# ADS8688.net
KiCad netlist of a schematic drawn in Altium Designer
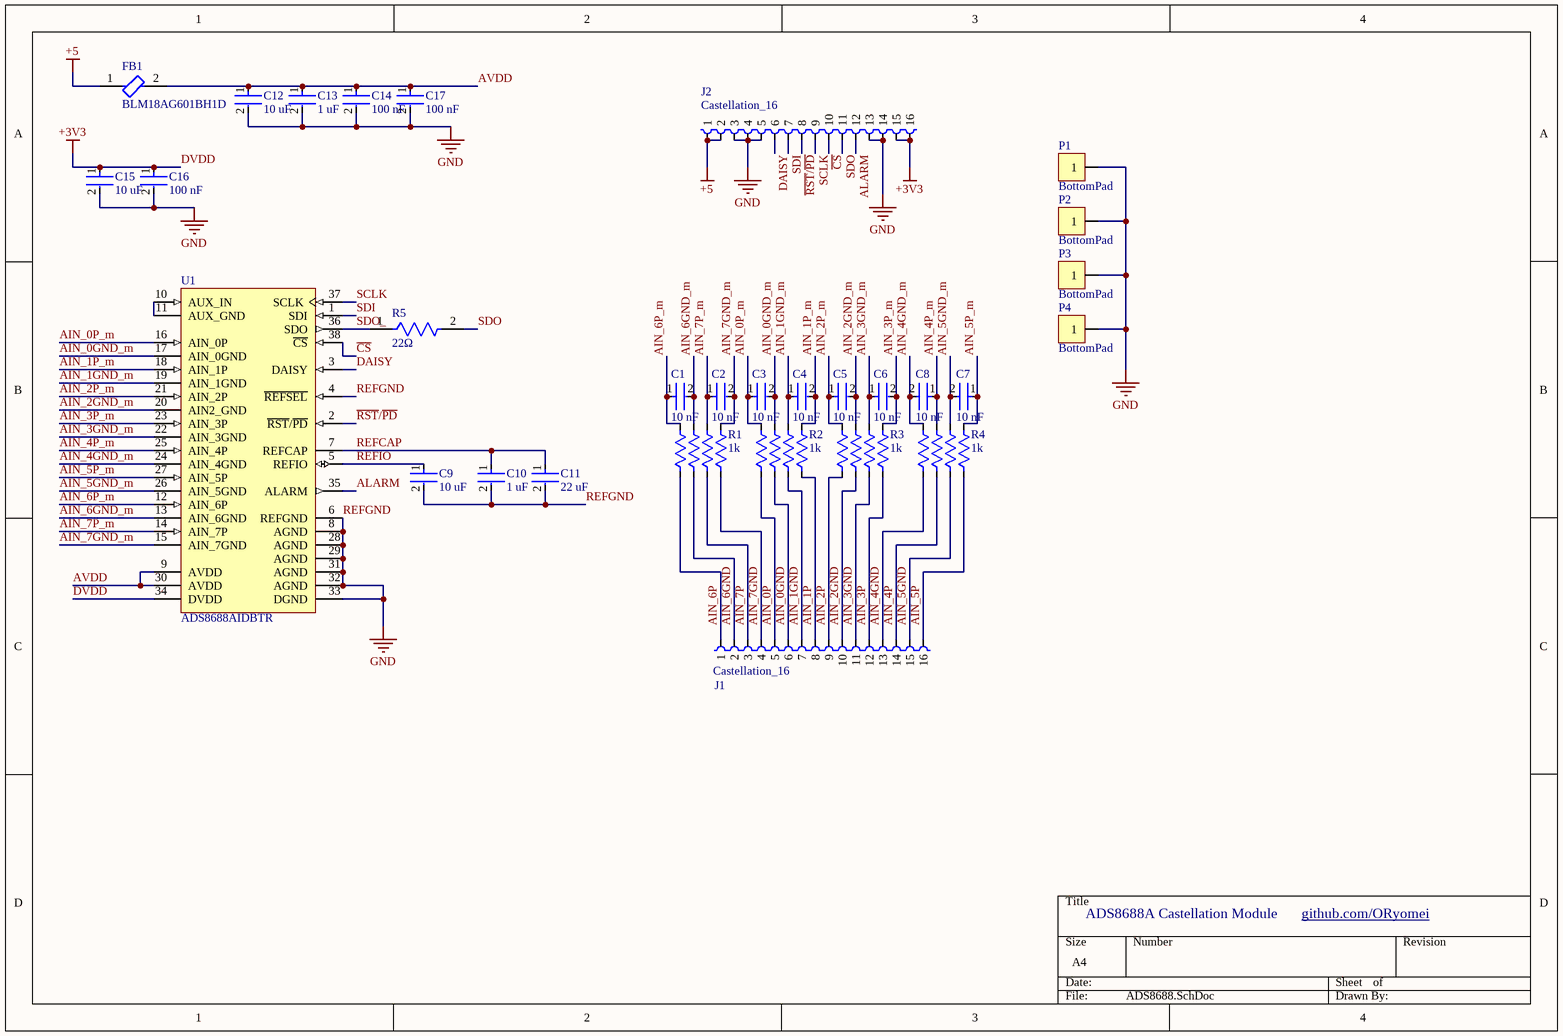
[diagram p0: ADS8688.SchDoc]

(export (version "E")
  (design (tool "Eeschema 10.0.6"))
  (components
    (comp (ref "C1")
      (value "10 nF")
      (footprint "FP-GRT188-0_1-e0_2_0_5-IPC_C")
      (description "Multi-Layer Ceramic Capacitor 10nF 25V C0G ±1% 0603 Paper T/R\r\nGRT1885C1E103FA02D\r\n0603")
      (libsource (lib "Altium Content Vault") (part "02cd4be3c70576c341d710602a673aa"))
    )
    (comp (ref "C2")
      (value "10 nF")
      (footprint "FP-GRT188-0_1-e0_2_0_5-IPC_C")
      (description "Multi-Layer Ceramic Capacitor 10nF 25V C0G ±1% 0603 Paper T/R\r\nGRT1885C1E103FA02D\r\n0603")
      (libsource (lib "Altium Content Vault") (part "02cd4be3c70576c341d710602a673aa"))
    )
    (comp (ref "C3")
      (value "10 nF")
      (footprint "FP-GRT188-0_1-e0_2_0_5-IPC_C")
      (description "Multi-Layer Ceramic Capacitor 10nF 25V C0G ±1% 0603 Paper T/R\r\nGRT1885C1E103FA02D\r\n0603")
      (libsource (lib "Altium Content Vault") (part "02cd4be3c70576c341d710602a673aa"))
    )
    (comp (ref "C4")
      (value "10 nF")
      (footprint "FP-GRT188-0_1-e0_2_0_5-IPC_C")
      (description "Multi-Layer Ceramic Capacitor 10nF 25V C0G ±1% 0603 Paper T/R\r\nGRT1885C1E103FA02D\r\n0603")
      (libsource (lib "Altium Content Vault") (part "02cd4be3c70576c341d710602a673aa"))
    )
    (comp (ref "C5")
      (value "10 nF")
      (footprint "FP-GRT188-0_1-e0_2_0_5-IPC_C")
      (description "Multi-Layer Ceramic Capacitor 10nF 25V C0G ±1% 0603 Paper T/R\r\nGRT1885C1E103FA02D\r\n0603")
      (libsource (lib "Altium Content Vault") (part "02cd4be3c70576c341d710602a673aa"))
    )
    (comp (ref "C6")
      (value "10 nF")
      (footprint "FP-GRT188-0_1-e0_2_0_5-IPC_C")
      (description "Multi-Layer Ceramic Capacitor 10nF 25V C0G ±1% 0603 Paper T/R\r\nGRT1885C1E103FA02D\r\n0603")
      (libsource (lib "Altium Content Vault") (part "02cd4be3c70576c341d710602a673aa"))
    )
    (comp (ref "C7")
      (value "10 nF")
      (footprint "FP-GRT188-0_1-e0_2_0_5-IPC_C")
      (description "Multi-Layer Ceramic Capacitor 10nF 25V C0G ±1% 0603 Paper T/R\r\nGRT1885C1E103FA02D\r\n0603")
      (libsource (lib "Altium Content Vault") (part "02cd4be3c70576c341d710602a673aa"))
    )
    (comp (ref "C8")
      (value "10 nF")
      (footprint "FP-GRT188-0_1-e0_2_0_5-IPC_C")
      (description "Multi-Layer Ceramic Capacitor 10nF 25V C0G ±1% 0603 Paper T/R\r\nGRT1885C1E103FA02D\r\n0603")
      (libsource (lib "Altium Content Vault") (part "02cd4be3c70576c341d710602a673aa"))
    )
    (comp (ref "C9")
      (value "10 uF")
      (footprint "FP-GRT188-0_2-MFG")
      (description "Multi-Layer Ceramic Capacitor 10uF 25V X5R ±20% 0603 Paper T/R\r\nGRT188R61E106ME13D\r\n10 uF")
      (fields (field (name "TOLERANCE") "20%"))
      (libsource (lib "Altium Content Vault") (part "02cd4be3c70576c341d710602a673aa"))
    )
    (comp (ref "C10")
      (value "1 uF")
      (footprint "FP-GRT188-0_1-e0_2_0_5-IPC_C")
      (description "Multi-Layer Ceramic Capacitor 1uF 25V X7R ±10% 0603 Paper T/R\r\nGRT188R71E105KE13D\r\n1 uF")
      (libsource (lib "Altium Content Vault") (part "02cd4be3c70576c341d710602a673aa"))
    )
    (comp (ref "C11")
      (value "22 uF")
      (footprint "FP-GRT21B-0_2-IPC_C")
      (description "Multi-Layer Ceramic Capacitor 22uF 25V X5R ±20% 0805 Emboss T/R\r\nGRT21BR61E226ME13L\r\n22 uF")
      (fields (field (name "TOLERANCE") "20%"))
      (libsource (lib "Altium Content Vault") (part "02cd4be3c70576c341d710602a673aa"))
    )
    (comp (ref "C12")
      (value "10 uF")
      (footprint "FP-GRT188-0_2-MFG")
      (description "Multi-Layer Ceramic Capacitor 10uF 25V X5R ±20% 0603 Paper T/R\r\nGRT188R61E106ME13D\r\n10 uF")
      (fields (field (name "TOLERANCE") "20%"))
      (libsource (lib "Altium Content Vault") (part "02cd4be3c70576c341d710602a673aa"))
    )
    (comp (ref "C13")
      (value "1 uF")
      (footprint "FP-GRT188-0_1-e0_2_0_5-IPC_C")
      (description "Multi-Layer Ceramic Capacitor 1uF 25V X7R ±10% 0603 Paper T/R\r\nGRT188R71E105KE13D\r\n1 uF")
      (libsource (lib "Altium Content Vault") (part "02cd4be3c70576c341d710602a673aa"))
    )
    (comp (ref "C14")
      (value "100 nF")
      (footprint "FP-GCM188-0_1-IPC_B")
      (libsource (lib "Altium Content Vault") (part "02cd4be3c70576c341d710602a673aa"))
    )
    (comp (ref "C15")
      (value "10 uF")
      (footprint "FP-GRT188-0_2-MFG")
      (description "Multi-Layer Ceramic Capacitor 10uF 25V X5R ±20% 0603 Paper T/R\r\nGRT188R61E106ME13D\r\n10 uF")
      (fields (field (name "TOLERANCE") "20%"))
      (libsource (lib "Altium Content Vault") (part "02cd4be3c70576c341d710602a673aa"))
    )
    (comp (ref "C16")
      (value "100 nF")
      (footprint "FP-GCM188-0_1-IPC_B")
      (libsource (lib "Altium Content Vault") (part "02cd4be3c70576c341d710602a673aa"))
    )
    (comp (ref "C17")
      (value "100 nF")
      (footprint "FP-GCM188-0_1-IPC_B")
      (libsource (lib "Altium Content Vault") (part "02cd4be3c70576c341d710602a673aa"))
    )
    (comp (ref "FB1")
      (value "BLM18AG601BH1D")
      (footprint "FP-BLM18-0_15-t0_8-IPC_B")
      (description "Chip Ferrite Bead, 0603, 600Ω @ 100MHz, 0.38Ω, 25%, 500mA")
      (libsource (lib "Altium Content Vault") (part "5f30dd21d616792df468990f7003faa"))
    )
    (comp (ref "J1")
      (value "Castellation_16")
      (footprint "Castellation_16_hole")
      (description "8 holes")
      (libsource (lib "ADS8688") (part "Castellation_16"))
    )
    (comp (ref "J2")
      (value "Castellation_16")
      (footprint "Castellation_16_hole")
      (description "8 holes")
      (libsource (lib "") (part "Castellation_16_1"))
    )
    (comp (ref "P1")
      (value "BottomPad")
      (footprint "BottomPad")
      (libsource (lib "ADS8688") (part "BottomPad"))
    )
    (comp (ref "P2")
      (value "BottomPad")
      (footprint "BottomPad")
      (libsource (lib "ADS8688") (part "BottomPad"))
    )
    (comp (ref "P3")
      (value "BottomPad")
      (footprint "BottomPad")
      (libsource (lib "ADS8688") (part "BottomPad"))
    )
    (comp (ref "P4")
      (value "BottomPad")
      (footprint "BottomPad")
      (libsource (lib "ADS8688") (part "BottomPad"))
    )
    (comp (ref "R1")
      (value "1k")
      (footprint "CAY16A-1001F4LF")
      (libsource (lib "ADS8688") (part "CAY16A-1001F4LF"))
    )
    (comp (ref "R2")
      (value "1k")
      (footprint "CAY16A-1001F4LF")
      (libsource (lib "ADS8688") (part "CAY16A-1001F4LF"))
    )
    (comp (ref "R3")
      (value "1k")
      (footprint "CAY16A-1001F4LF")
      (libsource (lib "ADS8688") (part "CAY16A-1001F4LF"))
    )
    (comp (ref "R4")
      (value "1k")
      (footprint "CAY16A-1001F4LF")
      (libsource (lib "ADS8688") (part "CAY16A-1001F4LF"))
    )
    (comp (ref "R5")
      (value "22Ω")
      (footprint "FP-AC0603-IPC_B")
      (description "RES 22Ω 5.00% 0.1W 0603\r\nAC0603JR-0722RL")
      (fields (field (name "TOLERANCE") "5%"))
      (libsource (lib "Altium Content Vault") (part "1029c3af85768c4190bb7ad29bc67b5"))
    )
    (comp (ref "U1")
      (value "ADS8688AIDBTR")
      (footprint "DBT38_N")
      (fields (field (name "MANUFACTURER") "Texas Instruments") (field (name "PARTNUMBER") "ADS8688IDBTR"))
      (libsource (lib "ADS8688") (part "ADS8688AIDBTR"))
    )
  )
  (nets
    (net (code "1") (name "+3V3") (class "Default")
      (node (ref "C15") (pin "1") (pinfunction "1_1") (pintype "passive"))
      (node (ref "C16") (pin "1") (pinfunction "1_1") (pintype "passive"))
      (node (ref "J2") (pin "15") (pinfunction "15_15") (pintype "passive"))
      (node (ref "J2") (pin "16") (pinfunction "16_16") (pintype "passive"))
      (node (ref "U1") (pin "34") (pinfunction "DVDD_34") (pintype "power_in"))
    )
    (net (code "2") (name "+5") (class "Default")
      (node (ref "FB1") (pin "1") (pinfunction "1_1") (pintype "passive"))
      (node (ref "J2") (pin "1") (pinfunction "1_1") (pintype "passive"))
      (node (ref "J2") (pin "2") (pinfunction "2_2") (pintype "passive"))
    )
    (net (code "3") (name "/AIN_0GND") (class "Default")
      (node (ref "J1") (pin "6") (pinfunction "6_6") (pintype "passive"))
      (node (ref "R2") (pin "6") (pinfunction "6_6") (pintype "passive"))
    )
    (net (code "4") (name "/AIN_0GND_m") (class "Default")
      (node (ref "C3") (pin "2") (pinfunction "2_2") (pintype "passive"))
      (node (ref "R2") (pin "3") (pinfunction "3_3") (pintype "passive"))
      (node (ref "U1") (pin "17") (pinfunction "AIN_0GND_17") (pintype "power_in"))
    )
    (net (code "5") (name "/AIN_0P") (class "Default")
      (node (ref "J1") (pin "5") (pinfunction "5_5") (pintype "passive"))
      (node (ref "R2") (pin "5") (pinfunction "5_5") (pintype "passive"))
    )
    (net (code "6") (name "/AIN_0P_m") (class "Default")
      (node (ref "C3") (pin "1") (pinfunction "1_1") (pintype "passive"))
      (node (ref "R2") (pin "4") (pinfunction "4_4") (pintype "passive"))
      (node (ref "U1") (pin "16") (pinfunction "AIN_0P_16") (pintype "input"))
    )
    (net (code "7") (name "/AIN_1GND") (class "Default")
      (node (ref "J1") (pin "7") (pinfunction "7_7") (pintype "passive"))
      (node (ref "R2") (pin "7") (pinfunction "7_7") (pintype "passive"))
    )
    (net (code "8") (name "/AIN_1GND_m") (class "Default")
      (node (ref "C4") (pin "1") (pinfunction "1_1") (pintype "passive"))
      (node (ref "R2") (pin "2") (pinfunction "2_2") (pintype "passive"))
      (node (ref "U1") (pin "19") (pinfunction "AIN_1GND_19") (pintype "power_in"))
    )
    (net (code "9") (name "/AIN_1P") (class "Default")
      (node (ref "J1") (pin "8") (pinfunction "8_8") (pintype "passive"))
      (node (ref "R2") (pin "8") (pinfunction "8_8") (pintype "passive"))
    )
    (net (code "10") (name "/AIN_1P_m") (class "Default")
      (node (ref "C4") (pin "2") (pinfunction "2_2") (pintype "passive"))
      (node (ref "R2") (pin "1") (pinfunction "1_1") (pintype "passive"))
      (node (ref "U1") (pin "18") (pinfunction "AIN_1P_18") (pintype "input"))
    )
    (net (code "11") (name "/AIN_2GND") (class "Default")
      (node (ref "J1") (pin "10") (pinfunction "10_10") (pintype "passive"))
      (node (ref "R3") (pin "6") (pinfunction "6_6") (pintype "passive"))
    )
    (net (code "12") (name "/AIN_2GND_m") (class "Default")
      (node (ref "C5") (pin "2") (pinfunction "2_2") (pintype "passive"))
      (node (ref "R3") (pin "3") (pinfunction "3_3") (pintype "passive"))
      (node (ref "U1") (pin "20") (pinfunction "AIN2_GND_20") (pintype "power_in"))
    )
    (net (code "13") (name "/AIN_2P") (class "Default")
      (node (ref "J1") (pin "9") (pinfunction "9_9") (pintype "passive"))
      (node (ref "R3") (pin "5") (pinfunction "5_5") (pintype "passive"))
    )
    (net (code "14") (name "/AIN_2P_m") (class "Default")
      (node (ref "C5") (pin "1") (pinfunction "1_1") (pintype "passive"))
      (node (ref "R3") (pin "4") (pinfunction "4_4") (pintype "passive"))
      (node (ref "U1") (pin "21") (pinfunction "AIN_2P_21") (pintype "input"))
    )
    (net (code "15") (name "/AIN_3GND") (class "Default")
      (node (ref "J1") (pin "11") (pinfunction "11_11") (pintype "passive"))
      (node (ref "R3") (pin "7") (pinfunction "7_7") (pintype "passive"))
    )
    (net (code "16") (name "/AIN_3GND_m") (class "Default")
      (node (ref "C6") (pin "1") (pinfunction "1_1") (pintype "passive"))
      (node (ref "R3") (pin "2") (pinfunction "2_2") (pintype "passive"))
      (node (ref "U1") (pin "22") (pinfunction "AIN_3GND_22") (pintype "power_in"))
    )
    (net (code "17") (name "/AIN_3P") (class "Default")
      (node (ref "J1") (pin "12") (pinfunction "12_12") (pintype "passive"))
      (node (ref "R3") (pin "8") (pinfunction "8_8") (pintype "passive"))
    )
    (net (code "18") (name "/AIN_3P_m") (class "Default")
      (node (ref "C6") (pin "2") (pinfunction "2_2") (pintype "passive"))
      (node (ref "R3") (pin "1") (pinfunction "1_1") (pintype "passive"))
      (node (ref "U1") (pin "23") (pinfunction "AIN_3P_23") (pintype "input"))
    )
    (net (code "19") (name "/AIN_4GND") (class "Default")
      (node (ref "J1") (pin "13") (pinfunction "13_13") (pintype "passive"))
      (node (ref "R4") (pin "5") (pinfunction "5_5") (pintype "passive"))
    )
    (net (code "20") (name "/AIN_4GND_m") (class "Default")
      (node (ref "C8") (pin "2") (pinfunction "2_2") (pintype "passive"))
      (node (ref "R4") (pin "4") (pinfunction "4_4") (pintype "passive"))
      (node (ref "U1") (pin "24") (pinfunction "AIN_4GND_24") (pintype "power_in"))
    )
    (net (code "21") (name "/AIN_4P") (class "Default")
      (node (ref "J1") (pin "14") (pinfunction "14_14") (pintype "passive"))
      (node (ref "R4") (pin "6") (pinfunction "6_6") (pintype "passive"))
    )
    (net (code "22") (name "/AIN_4P_m") (class "Default")
      (node (ref "C8") (pin "1") (pinfunction "1_1") (pintype "passive"))
      (node (ref "R4") (pin "3") (pinfunction "3_3") (pintype "passive"))
      (node (ref "U1") (pin "25") (pinfunction "AIN_4P_25") (pintype "input"))
    )
    (net (code "23") (name "/AIN_5GND") (class "Default")
      (node (ref "J1") (pin "15") (pinfunction "15_15") (pintype "passive"))
      (node (ref "R4") (pin "7") (pinfunction "7_7") (pintype "passive"))
    )
    (net (code "24") (name "/AIN_5GND_m") (class "Default")
      (node (ref "C7") (pin "2") (pinfunction "2_2") (pintype "passive"))
      (node (ref "R4") (pin "2") (pinfunction "2_2") (pintype "passive"))
      (node (ref "U1") (pin "26") (pinfunction "AIN_5GND_26") (pintype "power_in"))
    )
    (net (code "25") (name "/AIN_5P") (class "Default")
      (node (ref "J1") (pin "16") (pinfunction "16_16") (pintype "passive"))
      (node (ref "R4") (pin "8") (pinfunction "8_8") (pintype "passive"))
    )
    (net (code "26") (name "/AIN_5P_m") (class "Default")
      (node (ref "C7") (pin "1") (pinfunction "1_1") (pintype "passive"))
      (node (ref "R4") (pin "1") (pinfunction "1_1") (pintype "passive"))
      (node (ref "U1") (pin "27") (pinfunction "AIN_5P_27") (pintype "input"))
    )
    (net (code "27") (name "/AIN_6GND") (class "Default")
      (node (ref "J1") (pin "2") (pinfunction "2_2") (pintype "passive"))
      (node (ref "R1") (pin "2") (pinfunction "2_2") (pintype "passive"))
    )
    (net (code "28") (name "/AIN_6GND_m") (class "Default")
      (node (ref "C1") (pin "2") (pinfunction "2_2") (pintype "passive"))
      (node (ref "R1") (pin "7") (pinfunction "7_7") (pintype "passive"))
      (node (ref "U1") (pin "13") (pinfunction "AIN_6GND_13") (pintype "power_in"))
    )
    (net (code "29") (name "/AIN_6P") (class "Default")
      (node (ref "J1") (pin "1") (pinfunction "1_1") (pintype "passive"))
      (node (ref "R1") (pin "1") (pinfunction "1_1") (pintype "passive"))
    )
    (net (code "30") (name "/AIN_6P_m") (class "Default")
      (node (ref "C1") (pin "1") (pinfunction "1_1") (pintype "passive"))
      (node (ref "R1") (pin "8") (pinfunction "8_8") (pintype "passive"))
      (node (ref "U1") (pin "12") (pinfunction "AIN_6P_12") (pintype "input"))
    )
    (net (code "31") (name "/AIN_7GND") (class "Default")
      (node (ref "J1") (pin "4") (pinfunction "4_4") (pintype "passive"))
      (node (ref "R1") (pin "4") (pinfunction "4_4") (pintype "passive"))
    )
    (net (code "32") (name "/AIN_7GND_m") (class "Default")
      (node (ref "C2") (pin "2") (pinfunction "2_2") (pintype "passive"))
      (node (ref "R1") (pin "5") (pinfunction "5_5") (pintype "passive"))
      (node (ref "U1") (pin "15") (pinfunction "AIN_7GND_15") (pintype "power_in"))
    )
    (net (code "33") (name "/AIN_7P") (class "Default")
      (node (ref "J1") (pin "3") (pinfunction "3_3") (pintype "passive"))
      (node (ref "R1") (pin "3") (pinfunction "3_3") (pintype "passive"))
    )
    (net (code "34") (name "/AIN_7P_m") (class "Default")
      (node (ref "C2") (pin "1") (pinfunction "1_1") (pintype "passive"))
      (node (ref "R1") (pin "6") (pinfunction "6_6") (pintype "passive"))
      (node (ref "U1") (pin "14") (pinfunction "AIN_7P_14") (pintype "input"))
    )
    (net (code "35") (name "/ALARM") (class "Default")
      (node (ref "J2") (pin "12") (pinfunction "12_12") (pintype "passive"))
      (node (ref "U1") (pin "35") (pinfunction "ALARM_35") (pintype "output"))
    )
    (net (code "36") (name "/AVDD") (class "Default")
      (node (ref "C12") (pin "1") (pinfunction "1_1") (pintype "passive"))
      (node (ref "C13") (pin "1") (pinfunction "1_1") (pintype "passive"))
      (node (ref "C14") (pin "1") (pinfunction "1_1") (pintype "passive"))
      (node (ref "C17") (pin "1") (pinfunction "1_1") (pintype "passive"))
      (node (ref "FB1") (pin "2") (pinfunction "2_2") (pintype "passive"))
      (node (ref "U1") (pin "30") (pinfunction "AVDD_30") (pintype "power_in"))
      (node (ref "U1") (pin "9") (pinfunction "AVDD_9") (pintype "power_in"))
    )
    (net (code "37") (name "/DAISY") (class "Default")
      (node (ref "J2") (pin "6") (pinfunction "6_6") (pintype "passive"))
      (node (ref "U1") (pin "3") (pinfunction "DAISY_3") (pintype "input"))
    )
    (net (code "38") (name "/REFCAP") (class "Default")
      (node (ref "C10") (pin "1") (pinfunction "1_1") (pintype "passive"))
      (node (ref "C11") (pin "1") (pinfunction "1_1") (pintype "passive"))
      (node (ref "U1") (pin "7") (pinfunction "REFCAP_7") (pintype "passive"))
    )
    (net (code "39") (name "/REFIO") (class "Default")
      (node (ref "C9") (pin "1") (pinfunction "1_1") (pintype "passive"))
      (node (ref "U1") (pin "5") (pinfunction "REFIO_5") (pintype "bidirectional"))
    )
    (net (code "40") (name "/SCLK") (class "Default")
      (node (ref "J2") (pin "9") (pinfunction "9_9") (pintype "passive"))
      (node (ref "U1") (pin "37") (pinfunction "SCLK_37") (pintype "input"))
    )
    (net (code "41") (name "/SDI") (class "Default")
      (node (ref "J2") (pin "7") (pinfunction "7_7") (pintype "passive"))
      (node (ref "U1") (pin "1") (pinfunction "SDI_1") (pintype "input"))
    )
    (net (code "42") (name "/SDO") (class "Default")
      (node (ref "J2") (pin "11") (pinfunction "11_11") (pintype "passive"))
      (node (ref "R5") (pin "2") (pinfunction "2_2") (pintype "passive"))
    )
    (net (code "43") (name "/SDO_") (class "Default")
      (node (ref "R5") (pin "1") (pinfunction "1_1") (pintype "passive"))
      (node (ref "U1") (pin "36") (pinfunction "SDO_36") (pintype "output"))
    )
    (net (code "44") (name "/~{CS}") (class "Default")
      (node (ref "J2") (pin "10") (pinfunction "10_10") (pintype "passive"))
      (node (ref "U1") (pin "38") (pinfunction "~{CS}_38") (pintype "input"))
    )
    (net (code "45") (name "/~{RST}{slash}~{PD}") (class "Default")
      (node (ref "J2") (pin "8") (pinfunction "8_8") (pintype "passive"))
      (node (ref "U1") (pin "2") (pinfunction "~{RST}/~{PD}_2") (pintype "input"))
    )
    (net (code "46") (name "GND") (class "Default")
      (node (ref "C10") (pin "2") (pinfunction "2_2") (pintype "passive"))
      (node (ref "C11") (pin "2") (pinfunction "2_2") (pintype "passive"))
      (node (ref "C12") (pin "2") (pinfunction "2_2") (pintype "passive"))
      (node (ref "C13") (pin "2") (pinfunction "2_2") (pintype "passive"))
      (node (ref "C14") (pin "2") (pinfunction "2_2") (pintype "passive"))
      (node (ref "C15") (pin "2") (pinfunction "2_2") (pintype "passive"))
      (node (ref "C16") (pin "2") (pinfunction "2_2") (pintype "passive"))
      (node (ref "C17") (pin "2") (pinfunction "2_2") (pintype "passive"))
      (node (ref "C9") (pin "2") (pinfunction "2_2") (pintype "passive"))
      (node (ref "J2") (pin "13") (pinfunction "13_13") (pintype "passive"))
      (node (ref "J2") (pin "14") (pinfunction "14_14") (pintype "passive"))
      (node (ref "J2") (pin "3") (pinfunction "3_3") (pintype "passive"))
      (node (ref "J2") (pin "4") (pinfunction "4_4") (pintype "passive"))
      (node (ref "J2") (pin "5") (pinfunction "5_5") (pintype "passive"))
      (node (ref "P1") (pin "1") (pinfunction "1_1") (pintype "passive"))
      (node (ref "P2") (pin "1") (pinfunction "1_1") (pintype "passive"))
      (node (ref "P3") (pin "1") (pinfunction "1_1") (pintype "passive"))
      (node (ref "P4") (pin "1") (pinfunction "1_1") (pintype "passive"))
      (node (ref "U1") (pin "28") (pinfunction "AGND_28") (pintype "power_in"))
      (node (ref "U1") (pin "29") (pinfunction "AGND_29") (pintype "power_in"))
      (node (ref "U1") (pin "31") (pinfunction "AGND_31") (pintype "power_in"))
      (node (ref "U1") (pin "32") (pinfunction "AGND_32") (pintype "power_in"))
      (node (ref "U1") (pin "33") (pinfunction "DGND_33") (pintype "power_in"))
      (node (ref "U1") (pin "4") (pinfunction "~{REFSEL}_4") (pintype "input"))
      (node (ref "U1") (pin "6") (pinfunction "REFGND_6") (pintype "power_in"))
      (node (ref "U1") (pin "8") (pinfunction "AGND_8") (pintype "power_in"))
    )
    (net (code "47") (name "Net-(U1-AUX_GND)") (class "Default")
      (node (ref "U1") (pin "10") (pinfunction "AUX_IN_10") (pintype "input"))
      (node (ref "U1") (pin "11") (pinfunction "AUX_GND_11") (pintype "power_in"))
    )
  )
)
